# ICSP_board.net
KiCad netlist of a schematic drawn in EAGLE
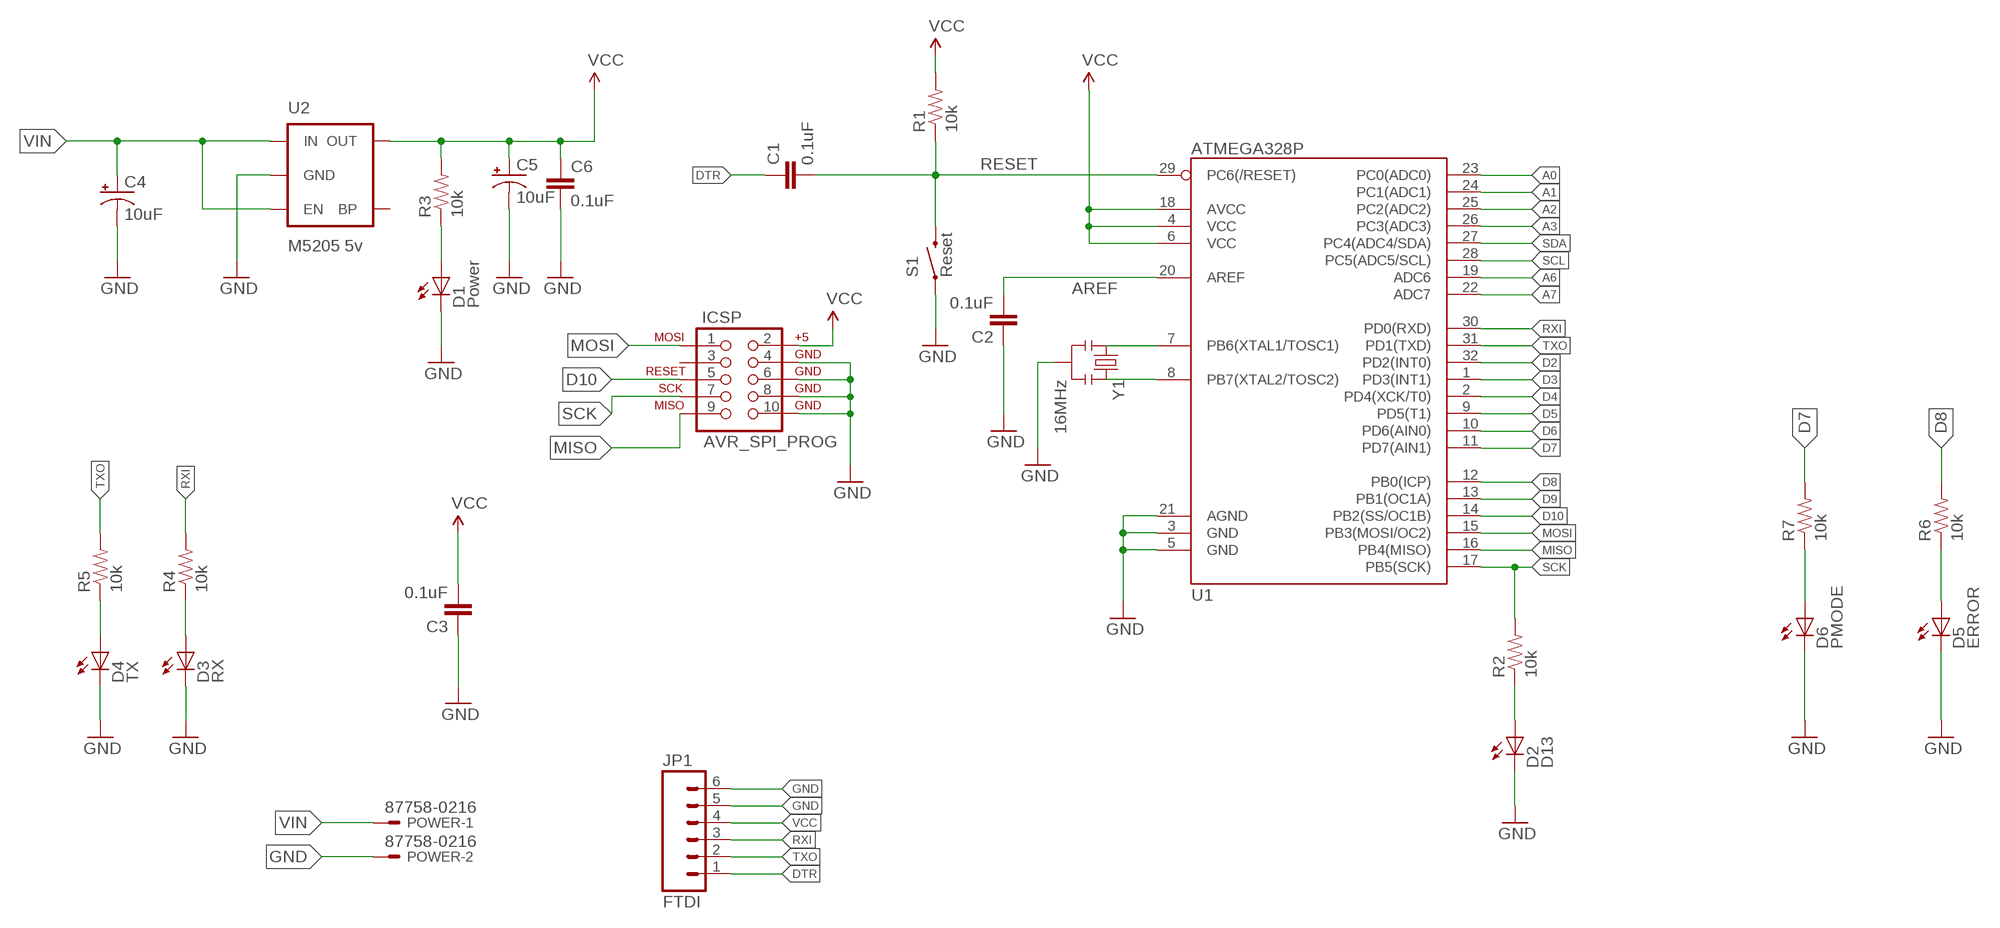
[diagram p0: schematic, sheet 1]

(export (version "E")
  (design (tool "Eeschema 10.0.6"))
  (components
    (comp (ref "C1")
      (value "0.1uF")
      (footprint "eagle-import:0603-CAP")
      (libsource (lib "eagle-import") (part "CAP0603-CAP"))
    )
    (comp (ref "C2")
      (value "0.1uF")
      (footprint "eagle-import:0603-CAP")
      (libsource (lib "eagle-import") (part "CAP0603-CAP"))
    )
    (comp (ref "C3")
      (value "0.1uF")
      (footprint "eagle-import:0603-CAP")
      (libsource (lib "eagle-import") (part "CAP0603-CAP"))
    )
    (comp (ref "C4")
      (value "10uF")
      (footprint "eagle-import:EIA3216")
      (libsource (lib "eagle-import") (part "CAP_POL1206"))
    )
    (comp (ref "C5")
      (value "10uF")
      (footprint "eagle-import:EIA3216")
      (libsource (lib "eagle-import") (part "CAP_POL1206"))
    )
    (comp (ref "C6")
      (value "0.1uF")
      (footprint "eagle-import:0603-CAP")
      (libsource (lib "eagle-import") (part "CAP0603-CAP"))
    )
    (comp (ref "D1")
      (value "Power")
      (footprint "eagle-import:LED-0603")
      (libsource (lib "eagle-import") (part "LED-RED0603"))
    )
    (comp (ref "D2")
      (value "D13")
      (footprint "eagle-import:LED-0603")
      (libsource (lib "eagle-import") (part "LED-RED0603"))
    )
    (comp (ref "D3")
      (value "RX")
      (footprint "eagle-import:LED-0603")
      (libsource (lib "eagle-import") (part "LED-GREEN0603"))
    )
    (comp (ref "D4")
      (value "TX")
      (footprint "eagle-import:LED-0603")
      (libsource (lib "eagle-import") (part "LED-RED0603"))
    )
    (comp (ref "D5")
      (value "ERROR")
      (footprint "eagle-import:LED-0603")
      (libsource (lib "eagle-import") (part "LED-GREEN0603"))
    )
    (comp (ref "D6")
      (value "PMODE")
      (footprint "eagle-import:LED-0603")
      (libsource (lib "eagle-import") (part "LED-GREEN0603"))
    )
    (comp (ref "ICSP")
      (value "AVR_SPI_PROG")
      (footprint "eagle-import:AVR_ICSP")
      (libsource (lib "eagle-import") (part "AVR_SPI_PROG"))
    )
    (comp (ref "JP1")
      (value "FTDI")
      (footprint "eagle-import:1X06")
      (libsource (lib "eagle-import") (part "M06SIP"))
    )
    (comp (ref "POWER")
      (value "87758-0216")
      (footprint "eagle-import:87758-0216")
      (libsource (lib "eagle-import") (part "87758-0216"))
    )
    (comp (ref "R1")
      (value "10k")
      (footprint "eagle-import:0603-RES")
      (libsource (lib "eagle-import") (part "RESISTOR0603-RES"))
    )
    (comp (ref "R2")
      (value "10k")
      (footprint "eagle-import:0603-RES")
      (libsource (lib "eagle-import") (part "RESISTOR0603-RES"))
    )
    (comp (ref "R3")
      (value "10k")
      (footprint "eagle-import:0603-RES")
      (libsource (lib "eagle-import") (part "RESISTOR0603-RES"))
    )
    (comp (ref "R4")
      (value "10k")
      (footprint "eagle-import:0603-RES")
      (libsource (lib "eagle-import") (part "RESISTOR0603-RES"))
    )
    (comp (ref "R5")
      (value "10k")
      (footprint "eagle-import:0603-RES")
      (libsource (lib "eagle-import") (part "RESISTOR0603-RES"))
    )
    (comp (ref "R6")
      (value "10k")
      (footprint "eagle-import:0603-RES")
      (libsource (lib "eagle-import") (part "RESISTOR0603-RES"))
    )
    (comp (ref "R7")
      (value "10k")
      (footprint "eagle-import:0603-RES")
      (libsource (lib "eagle-import") (part "RESISTOR0603-RES"))
    )
    (comp (ref "S1")
      (value "Reset")
      (footprint "eagle-import:TACTILE_SWITCH_SMD")
      (libsource (lib "eagle-import") (part "SWITCH-MOMENTARY-2SMD"))
    )
    (comp (ref "U1")
      (value "ATMEGA328P")
      (footprint "eagle-import:TQFP32-08")
      (libsource (lib "eagle-import") (part "ATMEGA328_SMT"))
    )
    (comp (ref "U2")
      (value "M5205 5v")
      (footprint "eagle-import:SOT23-5")
      (libsource (lib "eagle-import") (part "MIC52055V"))
    )
    (comp (ref "Y1")
      (value "16MHz")
      (footprint "eagle-import:RESONATOR-SMD")
      (libsource (lib "eagle-import") (part "RESONATOR16MHZ"))
    )
  )
  (nets
    (net (code "1") (name "/AREF") (class "Default")
      (node (ref "C2") (pin "2") (pinfunction "2_2") (pintype "passive"))
      (node (ref "U1") (pin "20") (pinfunction "AREF_20") (pintype "bidirectional"))
    )
    (net (code "2") (name "/RESET") (class "Default")
      (node (ref "C1") (pin "2") (pinfunction "2_2") (pintype "passive"))
      (node (ref "R1") (pin "1") (pinfunction "1_1") (pintype "passive"))
      (node (ref "S1") (pin "3") (pinfunction "2_3") (pintype "passive"))
      (node (ref "U1") (pin "29") (pinfunction "PC6(/RESET)_29") (pintype "bidirectional"))
    )
    (net (code "3") (name "A0") (class "Default")
      (node (ref "U1") (pin "23") (pinfunction "PC0(ADC0)_23") (pintype "bidirectional"))
    )
    (net (code "4") (name "A1") (class "Default")
      (node (ref "U1") (pin "24") (pinfunction "PC1(ADC1)_24") (pintype "bidirectional"))
    )
    (net (code "5") (name "A2") (class "Default")
      (node (ref "U1") (pin "25") (pinfunction "PC2(ADC2)_25") (pintype "bidirectional"))
    )
    (net (code "6") (name "A3") (class "Default")
      (node (ref "U1") (pin "26") (pinfunction "PC3(ADC3)_26") (pintype "bidirectional"))
    )
    (net (code "7") (name "A6") (class "Default")
      (node (ref "U1") (pin "19") (pinfunction "ADC6_19") (pintype "bidirectional"))
    )
    (net (code "8") (name "A7") (class "Default")
      (node (ref "U1") (pin "22") (pinfunction "ADC7_22") (pintype "bidirectional"))
    )
    (net (code "9") (name "D2") (class "Default")
      (node (ref "U1") (pin "32") (pinfunction "PD2(INT0)_32") (pintype "bidirectional"))
    )
    (net (code "10") (name "D3") (class "Default")
      (node (ref "U1") (pin "1") (pinfunction "PD3(INT1)_1") (pintype "bidirectional"))
    )
    (net (code "11") (name "D4") (class "Default")
      (node (ref "U1") (pin "2") (pinfunction "PD4(XCK/T0)_2") (pintype "bidirectional"))
    )
    (net (code "12") (name "D5") (class "Default")
      (node (ref "U1") (pin "9") (pinfunction "PD5(T1)_9") (pintype "bidirectional"))
    )
    (net (code "13") (name "D6") (class "Default")
      (node (ref "U1") (pin "10") (pinfunction "PD6(AIN0)_10") (pintype "bidirectional"))
    )
    (net (code "14") (name "D7") (class "Default")
      (node (ref "R7") (pin "2") (pinfunction "2_2") (pintype "passive"))
      (node (ref "U1") (pin "11") (pinfunction "PD7(AIN1)_11") (pintype "bidirectional"))
    )
    (net (code "15") (name "D8") (class "Default")
      (node (ref "R6") (pin "2") (pinfunction "2_2") (pintype "passive"))
      (node (ref "U1") (pin "12") (pinfunction "PB0(ICP)_12") (pintype "bidirectional"))
    )
    (net (code "16") (name "D9") (class "Default")
      (node (ref "U1") (pin "13") (pinfunction "PB1(OC1A)_13") (pintype "bidirectional"))
    )
    (net (code "17") (name "D10") (class "Default")
      (node (ref "ICSP") (pin "5") (pinfunction "5_5") (pintype "passive"))
      (node (ref "U1") (pin "14") (pinfunction "PB2(SS/OC1B)_14") (pintype "bidirectional"))
    )
    (net (code "18") (name "DTR") (class "Default")
      (node (ref "C1") (pin "1") (pinfunction "1_1") (pintype "passive"))
      (node (ref "JP1") (pin "1") (pinfunction "1_1") (pintype "passive"))
    )
    (net (code "19") (name "GND") (class "Default")
      (node (ref "C2") (pin "1") (pinfunction "1_1") (pintype "passive"))
      (node (ref "C3") (pin "1") (pinfunction "1_1") (pintype "passive"))
      (node (ref "C4") (pin "C") (pinfunction "-_C") (pintype "passive"))
      (node (ref "C5") (pin "C") (pinfunction "-_C") (pintype "passive"))
      (node (ref "C6") (pin "2") (pinfunction "2_2") (pintype "passive"))
      (node (ref "D1") (pin "C") (pinfunction "C_C") (pintype "passive"))
      (node (ref "D2") (pin "C") (pinfunction "C_C") (pintype "passive"))
      (node (ref "D3") (pin "C") (pinfunction "C_C") (pintype "passive"))
      (node (ref "D4") (pin "C") (pinfunction "C_C") (pintype "passive"))
      (node (ref "D5") (pin "C") (pinfunction "C_C") (pintype "passive"))
      (node (ref "D6") (pin "C") (pinfunction "C_C") (pintype "passive"))
      (node (ref "ICSP") (pin "10") (pinfunction "10_10") (pintype "passive"))
      (node (ref "ICSP") (pin "4") (pinfunction "4_4") (pintype "passive"))
      (node (ref "ICSP") (pin "6") (pinfunction "6_6") (pintype "passive"))
      (node (ref "ICSP") (pin "8") (pinfunction "8_8") (pintype "passive"))
      (node (ref "JP1") (pin "5") (pinfunction "5_5") (pintype "passive"))
      (node (ref "JP1") (pin "6") (pinfunction "6_6") (pintype "passive"))
      (node (ref "POWER") (pin "2") (pinfunction "S_2") (pintype "passive"))
      (node (ref "S1") (pin "1") (pinfunction "1_1") (pintype "passive"))
      (node (ref "U1") (pin "21") (pinfunction "AGND_21") (pintype "bidirectional"))
      (node (ref "U1") (pin "3") (pinfunction "GND_3") (pintype "bidirectional"))
      (node (ref "U1") (pin "5") (pinfunction "GND_5") (pintype "bidirectional"))
      (node (ref "U2") (pin "2") (pinfunction "GND_2") (pintype "input"))
      (node (ref "Y1") (pin "2") (pinfunction "2_2") (pintype "passive"))
    )
    (net (code "20") (name "MISO") (class "Default")
      (node (ref "ICSP") (pin "9") (pinfunction "9_9") (pintype "passive"))
      (node (ref "U1") (pin "16") (pinfunction "PB4(MISO)_16") (pintype "bidirectional"))
    )
    (net (code "21") (name "MOSI") (class "Default")
      (node (ref "ICSP") (pin "1") (pinfunction "1_1") (pintype "passive"))
      (node (ref "U1") (pin "15") (pinfunction "PB3(MOSI/OC2)_15") (pintype "bidirectional"))
    )
    (net (code "22") (name "Net-(D1-PadA)") (class "Default")
      (node (ref "D1") (pin "A") (pinfunction "A_A") (pintype "passive"))
      (node (ref "R3") (pin "1") (pinfunction "1_1") (pintype "passive"))
    )
    (net (code "23") (name "Net-(D2-PadA)") (class "Default")
      (node (ref "D2") (pin "A") (pinfunction "A_A") (pintype "passive"))
      (node (ref "R2") (pin "1") (pinfunction "1_1") (pintype "passive"))
    )
    (net (code "24") (name "Net-(D3-PadA)") (class "Default")
      (node (ref "D3") (pin "A") (pinfunction "A_A") (pintype "passive"))
      (node (ref "R4") (pin "1") (pinfunction "1_1") (pintype "passive"))
    )
    (net (code "25") (name "Net-(D4-PadA)") (class "Default")
      (node (ref "D4") (pin "A") (pinfunction "A_A") (pintype "passive"))
      (node (ref "R5") (pin "1") (pinfunction "1_1") (pintype "passive"))
    )
    (net (code "26") (name "Net-(D5-PadA)") (class "Default")
      (node (ref "D5") (pin "A") (pinfunction "A_A") (pintype "passive"))
      (node (ref "R6") (pin "1") (pinfunction "1_1") (pintype "passive"))
    )
    (net (code "27") (name "Net-(D6-PadA)") (class "Default")
      (node (ref "D6") (pin "A") (pinfunction "A_A") (pintype "passive"))
      (node (ref "R7") (pin "1") (pinfunction "1_1") (pintype "passive"))
    )
    (net (code "28") (name "Net-(U1-PB6(XTAL1{slash}TOSC1))") (class "Default")
      (node (ref "U1") (pin "7") (pinfunction "PB6(XTAL1/TOSC1)_7") (pintype "bidirectional"))
      (node (ref "Y1") (pin "1") (pinfunction "1_1") (pintype "passive"))
    )
    (net (code "29") (name "Net-(U1-PB7(XTAL2{slash}TOSC2))") (class "Default")
      (node (ref "U1") (pin "8") (pinfunction "PB7(XTAL2/TOSC2)_8") (pintype "bidirectional"))
      (node (ref "Y1") (pin "3") (pinfunction "3_3") (pintype "passive"))
    )
    (net (code "30") (name "RXI") (class "Default")
      (node (ref "JP1") (pin "3") (pinfunction "3_3") (pintype "passive"))
      (node (ref "R4") (pin "2") (pinfunction "2_2") (pintype "passive"))
      (node (ref "U1") (pin "30") (pinfunction "PD0(RXD)_30") (pintype "bidirectional"))
    )
    (net (code "31") (name "SCK") (class "Default")
      (node (ref "ICSP") (pin "7") (pinfunction "7_7") (pintype "passive"))
      (node (ref "R2") (pin "2") (pinfunction "2_2") (pintype "passive"))
      (node (ref "U1") (pin "17") (pinfunction "PB5(SCK)_17") (pintype "bidirectional"))
    )
    (net (code "32") (name "SCL") (class "Default")
      (node (ref "U1") (pin "28") (pinfunction "PC5(ADC5/SCL)_28") (pintype "bidirectional"))
    )
    (net (code "33") (name "SDA") (class "Default")
      (node (ref "U1") (pin "27") (pinfunction "PC4(ADC4/SDA)_27") (pintype "bidirectional"))
    )
    (net (code "34") (name "TXO") (class "Default")
      (node (ref "JP1") (pin "2") (pinfunction "2_2") (pintype "passive"))
      (node (ref "R5") (pin "2") (pinfunction "2_2") (pintype "passive"))
      (node (ref "U1") (pin "31") (pinfunction "PD1(TXD)_31") (pintype "bidirectional"))
    )
    (net (code "35") (name "VCC") (class "Default")
      (node (ref "C3") (pin "2") (pinfunction "2_2") (pintype "passive"))
      (node (ref "C5") (pin "A") (pinfunction "+_A") (pintype "passive"))
      (node (ref "C6") (pin "1") (pinfunction "1_1") (pintype "passive"))
      (node (ref "ICSP") (pin "2") (pinfunction "2_2") (pintype "passive"))
      (node (ref "JP1") (pin "4") (pinfunction "4_4") (pintype "passive"))
      (node (ref "R1") (pin "2") (pinfunction "2_2") (pintype "passive"))
      (node (ref "R3") (pin "2") (pinfunction "2_2") (pintype "passive"))
      (node (ref "U1") (pin "18") (pinfunction "AVCC_18") (pintype "bidirectional"))
      (node (ref "U1") (pin "4") (pinfunction "VCC_4") (pintype "bidirectional"))
      (node (ref "U1") (pin "6") (pinfunction "VCC_6") (pintype "bidirectional"))
      (node (ref "U2") (pin "5") (pinfunction "OUT_5") (pintype "passive"))
    )
    (net (code "36") (name "VIN") (class "Default")
      (node (ref "C4") (pin "A") (pinfunction "+_A") (pintype "passive"))
      (node (ref "POWER") (pin "1") (pinfunction "S_1") (pintype "passive"))
      (node (ref "U2") (pin "1") (pinfunction "IN_1") (pintype "input"))
      (node (ref "U2") (pin "3") (pinfunction "EN_3") (pintype "input"))
    )
    (net (code "37") (name "unconnected-(ICSP-Pad3)") (class "Default")
      (node (ref "ICSP") (pin "3") (pinfunction "3_3") (pintype "passive"))
    )
    (net (code "38") (name "unconnected-(U2-BP-Pad4)") (class "Default")
      (node (ref "U2") (pin "4") (pinfunction "BP_4") (pintype "input"))
    )
  )
)
